# piano.net
KiCad netlist of a schematic drawn in EAGLE
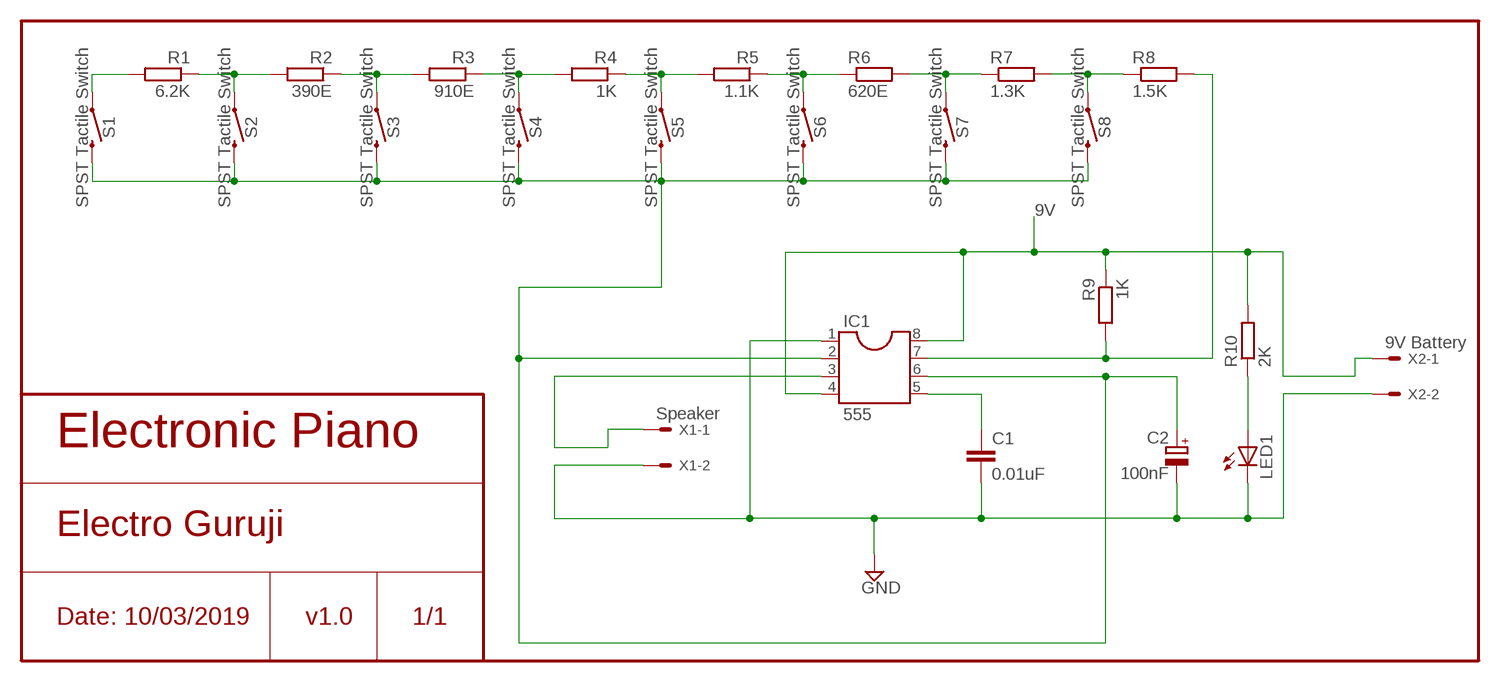
[diagram p0: schematic, sheet 1]

(export (version "E")
  (design (tool "Eeschema 10.0.6"))
  (components
    (comp (ref "C1")
      (value "0.01uF")
      (footprint "eagle-import:C025-024X044")
      (libsource (lib "eagle-import") (part "C-EU025-024X044"))
    )
    (comp (ref "C2")
      (value "100nF")
      (footprint "eagle-import:E5-5")
      (libsource (lib "eagle-import") (part "CPOL-EUE5-5"))
    )
    (comp (ref "IC1")
      (value "555")
      (footprint "eagle-import:SOCKET-08")
      (libsource (lib "eagle-import") (part "DIL8S"))
    )
    (comp (ref "LED1")
      (value "LED5MM")
      (footprint "eagle-import:LED5MM")
      (libsource (lib "eagle-import") (part "LED5MM"))
    )
    (comp (ref "R1")
      (value "6.2K")
      (footprint "eagle-import:0204_5")
      (libsource (lib "eagle-import") (part "R-EU_0204/5"))
    )
    (comp (ref "R2")
      (value "390E")
      (footprint "eagle-import:0204_5")
      (libsource (lib "eagle-import") (part "R-EU_0204/5"))
    )
    (comp (ref "R3")
      (value "910E")
      (footprint "eagle-import:0204_5")
      (libsource (lib "eagle-import") (part "R-EU_0204/5"))
    )
    (comp (ref "R4")
      (value "1K")
      (footprint "eagle-import:0204_5")
      (libsource (lib "eagle-import") (part "R-EU_0204/5"))
    )
    (comp (ref "R5")
      (value "1.1K")
      (footprint "eagle-import:0204_5")
      (libsource (lib "eagle-import") (part "R-EU_0204/5"))
    )
    (comp (ref "R6")
      (value "620E")
      (footprint "eagle-import:0204_5")
      (libsource (lib "eagle-import") (part "R-EU_0204/5"))
    )
    (comp (ref "R7")
      (value "1.3K")
      (footprint "eagle-import:0204_5")
      (libsource (lib "eagle-import") (part "R-EU_0204/5"))
    )
    (comp (ref "R8")
      (value "1.5K")
      (footprint "eagle-import:0204_5")
      (libsource (lib "eagle-import") (part "R-EU_0204/5"))
    )
    (comp (ref "R9")
      (value "1K")
      (footprint "eagle-import:0204_5")
      (libsource (lib "eagle-import") (part "R-EU_0204/5"))
    )
    (comp (ref "R10")
      (value "2K")
      (footprint "eagle-import:0204_5")
      (libsource (lib "eagle-import") (part "R-EU_0204/5"))
    )
    (comp (ref "S1")
      (value "SPST Tactile Switch")
      (footprint "eagle-import:TACTILE_SWITCH_PTH_6.0MM")
      (libsource (lib "eagle-import") (part "MOMENTARY-SWITCH-SPST-PTH-6.0MM"))
    )
    (comp (ref "S2")
      (value "SPST Tactile Switch")
      (footprint "eagle-import:TACTILE_SWITCH_PTH_6.0MM")
      (libsource (lib "eagle-import") (part "MOMENTARY-SWITCH-SPST-PTH-6.0MM"))
    )
    (comp (ref "S3")
      (value "SPST Tactile Switch")
      (footprint "eagle-import:TACTILE_SWITCH_PTH_6.0MM")
      (libsource (lib "eagle-import") (part "MOMENTARY-SWITCH-SPST-PTH-6.0MM"))
    )
    (comp (ref "S4")
      (value "SPST Tactile Switch")
      (footprint "eagle-import:TACTILE_SWITCH_PTH_6.0MM")
      (libsource (lib "eagle-import") (part "MOMENTARY-SWITCH-SPST-PTH-6.0MM"))
    )
    (comp (ref "S5")
      (value "SPST Tactile Switch")
      (footprint "eagle-import:TACTILE_SWITCH_PTH_6.0MM")
      (libsource (lib "eagle-import") (part "MOMENTARY-SWITCH-SPST-PTH-6.0MM"))
    )
    (comp (ref "S6")
      (value "SPST Tactile Switch")
      (footprint "eagle-import:TACTILE_SWITCH_PTH_6.0MM")
      (libsource (lib "eagle-import") (part "MOMENTARY-SWITCH-SPST-PTH-6.0MM"))
    )
    (comp (ref "S7")
      (value "SPST Tactile Switch")
      (footprint "eagle-import:TACTILE_SWITCH_PTH_6.0MM")
      (libsource (lib "eagle-import") (part "MOMENTARY-SWITCH-SPST-PTH-6.0MM"))
    )
    (comp (ref "S8")
      (value "SPST Tactile Switch")
      (footprint "eagle-import:TACTILE_SWITCH_PTH_6.0MM")
      (libsource (lib "eagle-import") (part "MOMENTARY-SWITCH-SPST-PTH-6.0MM"))
    )
    (comp (ref "X1")
      (value "Speaker")
      (footprint "eagle-import:KK-156-2")
      (fields (field (name "MF") "MOLEX"))
      (libsource (lib "eagle-import") (part "KK-156-2"))
    )
    (comp (ref "X2")
      (value "9V Battery")
      (footprint "eagle-import:KK-156-2")
      (fields (field (name "MF") "MOLEX"))
      (libsource (lib "eagle-import") (part "KK-156-2"))
    )
  )
  (nets
    (net (code "1") (name "/9V") (class "Default")
      (node (ref "IC1") (pin "4") (pinfunction "4_4") (pintype "passive"))
      (node (ref "IC1") (pin "8") (pinfunction "8_8") (pintype "passive"))
      (node (ref "R10") (pin "2") (pinfunction "2_2") (pintype "passive"))
      (node (ref "R9") (pin "1") (pinfunction "1_1") (pintype "passive"))
      (node (ref "X2") (pin "1") (pinfunction "S_1") (pintype "passive"))
    )
    (net (code "2") (name "GND") (class "Default")
      (node (ref "C1") (pin "2") (pinfunction "2_2") (pintype "passive"))
      (node (ref "C2") (pin "-") (pinfunction "-_-") (pintype "passive"))
      (node (ref "IC1") (pin "1") (pinfunction "1_1") (pintype "passive"))
      (node (ref "LED1") (pin "K") (pinfunction "C_K") (pintype "passive"))
      (node (ref "X1") (pin "2") (pinfunction "S_2") (pintype "passive"))
      (node (ref "X2") (pin "2") (pinfunction "S_2") (pintype "passive"))
    )
    (net (code "3") (name "Net-(C1-Pad1)") (class "Default")
      (node (ref "C1") (pin "1") (pinfunction "1_1") (pintype "passive"))
      (node (ref "IC1") (pin "5") (pinfunction "5_5") (pintype "passive"))
    )
    (net (code "4") (name "Net-(IC1-Pad7)") (class "Default")
      (node (ref "IC1") (pin "7") (pinfunction "7_7") (pintype "passive"))
      (node (ref "R8") (pin "2") (pinfunction "2_2") (pintype "passive"))
      (node (ref "R9") (pin "2") (pinfunction "2_2") (pintype "passive"))
    )
    (net (code "5") (name "Net-(LED1-PadA)") (class "Default")
      (node (ref "LED1") (pin "A") (pinfunction "A_A") (pintype "passive"))
      (node (ref "R10") (pin "1") (pinfunction "1_1") (pintype "passive"))
    )
    (net (code "6") (name "Net-(R1-Pad1)") (class "Default")
      (node (ref "R1") (pin "1") (pinfunction "1_1") (pintype "passive"))
      (node (ref "R2") (pin "2") (pinfunction "2_2") (pintype "passive"))
      (node (ref "S2") (pin "1") (pinfunction "1_1") (pintype "passive"))
    )
    (net (code "7") (name "Net-(R1-Pad2)") (class "Default")
      (node (ref "R1") (pin "2") (pinfunction "2_2") (pintype "passive"))
      (node (ref "S1") (pin "1") (pinfunction "1_1") (pintype "passive"))
    )
    (net (code "8") (name "Net-(R2-Pad1)") (class "Default")
      (node (ref "R2") (pin "1") (pinfunction "1_1") (pintype "passive"))
      (node (ref "R3") (pin "2") (pinfunction "2_2") (pintype "passive"))
      (node (ref "S3") (pin "1") (pinfunction "1_1") (pintype "passive"))
    )
    (net (code "9") (name "Net-(R3-Pad1)") (class "Default")
      (node (ref "R3") (pin "1") (pinfunction "1_1") (pintype "passive"))
      (node (ref "R4") (pin "2") (pinfunction "2_2") (pintype "passive"))
      (node (ref "S4") (pin "1") (pinfunction "1_1") (pintype "passive"))
    )
    (net (code "10") (name "Net-(R4-Pad1)") (class "Default")
      (node (ref "R4") (pin "1") (pinfunction "1_1") (pintype "passive"))
      (node (ref "R5") (pin "2") (pinfunction "2_2") (pintype "passive"))
      (node (ref "S5") (pin "1") (pinfunction "1_1") (pintype "passive"))
    )
    (net (code "11") (name "Net-(R5-Pad1)") (class "Default")
      (node (ref "R5") (pin "1") (pinfunction "1_1") (pintype "passive"))
      (node (ref "R6") (pin "1") (pinfunction "1_1") (pintype "passive"))
      (node (ref "S6") (pin "1") (pinfunction "1_1") (pintype "passive"))
    )
    (net (code "12") (name "Net-(R6-Pad2)") (class "Default")
      (node (ref "R6") (pin "2") (pinfunction "2_2") (pintype "passive"))
      (node (ref "R7") (pin "1") (pinfunction "1_1") (pintype "passive"))
      (node (ref "S7") (pin "1") (pinfunction "1_1") (pintype "passive"))
    )
    (net (code "13") (name "Net-(R7-Pad2)") (class "Default")
      (node (ref "R7") (pin "2") (pinfunction "2_2") (pintype "passive"))
      (node (ref "R8") (pin "1") (pinfunction "1_1") (pintype "passive"))
      (node (ref "S8") (pin "1") (pinfunction "1_1") (pintype "passive"))
    )
    (net (code "14") (name "Net-(S1-2)") (class "Default")
      (node (ref "C2") (pin "+") (pinfunction "+_+") (pintype "passive"))
      (node (ref "IC1") (pin "2") (pinfunction "2_2") (pintype "passive"))
      (node (ref "IC1") (pin "6") (pinfunction "6_6") (pintype "passive"))
      (node (ref "S1") (pin "3") (pinfunction "2_3") (pintype "passive"))
      (node (ref "S2") (pin "3") (pinfunction "2_3") (pintype "passive"))
      (node (ref "S3") (pin "3") (pinfunction "2_3") (pintype "passive"))
      (node (ref "S4") (pin "3") (pinfunction "2_3") (pintype "passive"))
      (node (ref "S5") (pin "3") (pinfunction "2_3") (pintype "passive"))
      (node (ref "S6") (pin "3") (pinfunction "2_3") (pintype "passive"))
      (node (ref "S7") (pin "3") (pinfunction "2_3") (pintype "passive"))
      (node (ref "S8") (pin "3") (pinfunction "2_3") (pintype "passive"))
    )
    (net (code "15") (name "Net-(X1A-S)") (class "Default")
      (node (ref "IC1") (pin "3") (pinfunction "3_3") (pintype "passive"))
      (node (ref "X1") (pin "1") (pinfunction "S_1") (pintype "passive"))
    )
  )
)
